# PCB_Schematic.net
KiCad netlist of a schematic drawn in Altium Designer
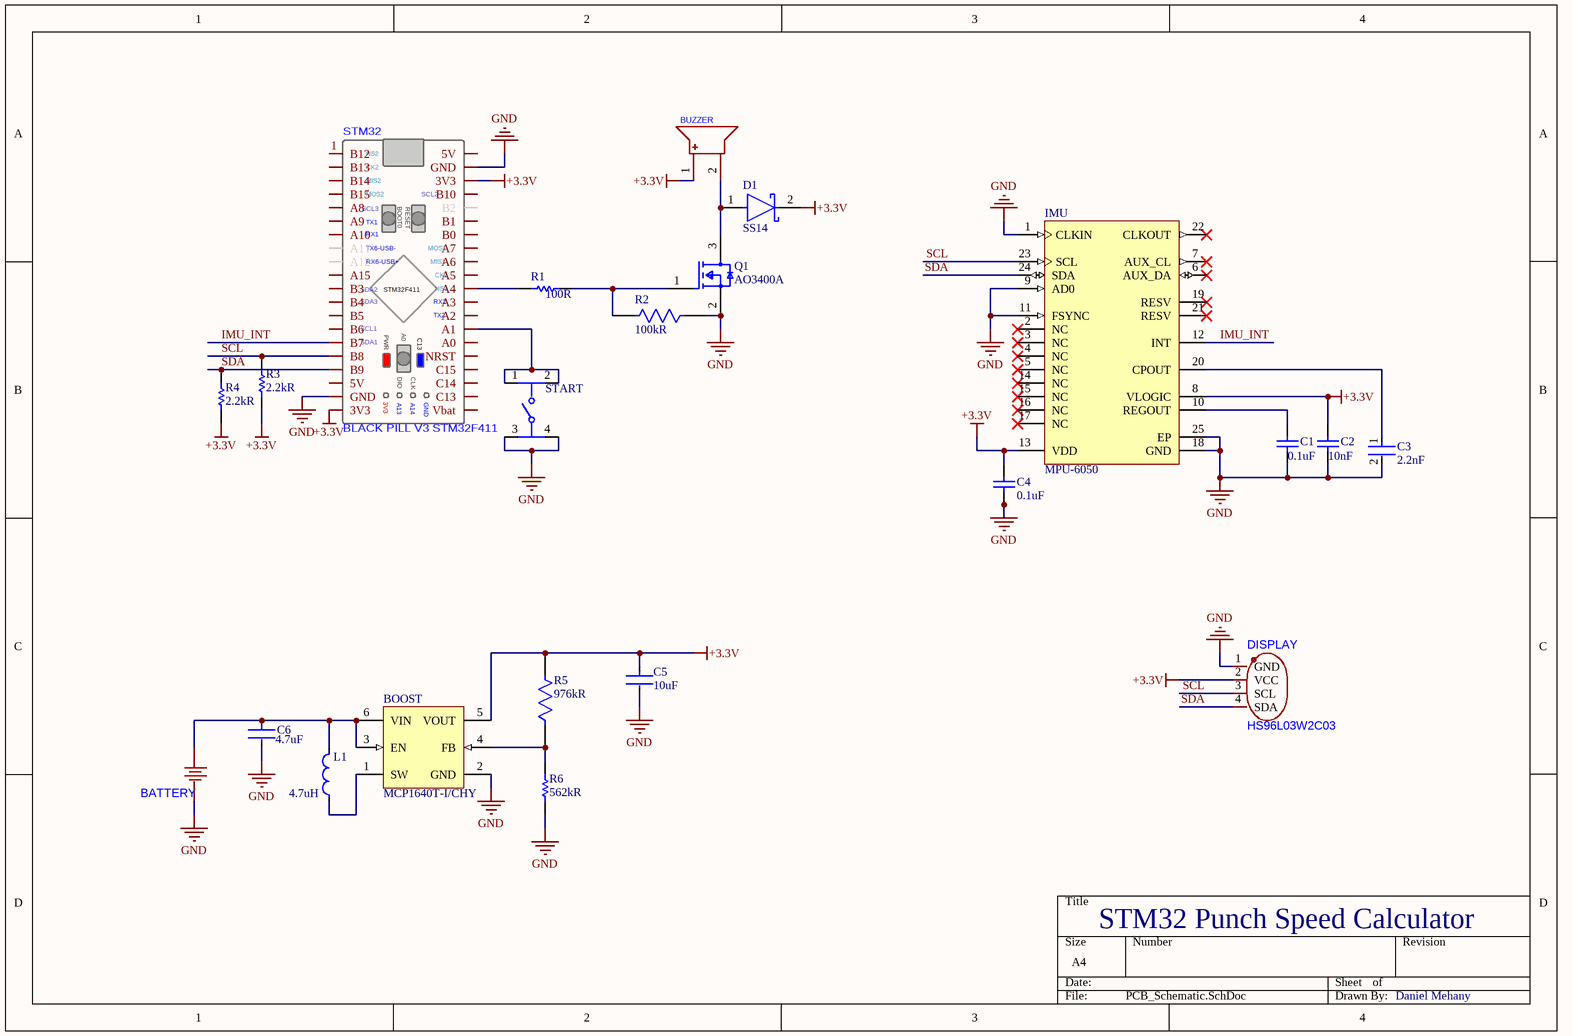
[diagram p0: PCB_Schematic.SchDoc]

(export (version "E")
  (design (tool "Eeschema 10.0.6"))
  (components
    (comp (ref "BATTERY")
      (value "BH-AAA-B5BA021")
      (footprint "BAT-SMD_BH-AAA-B5BA021")
      (fields (field (name "MANUFACTURER") "MYOUNG(美阳)") (field (name "JLCPCB PART #") "C7525446"))
      (libsource (lib "BH-AAA-B5BA0211_BH-AAA-B5BA021") (part "BH-AAA-B5BA021"))
    )
    (comp (ref "BOOST")
      (value "MCP1640T-I/CHY")
      (footprint "MCHP-SOT-23-CHY6_N")
      (fields (field (name "MANUFACTURER") "Microchip") (field (name "JLCPCB PART #") "C44365"))
      (libsource (lib "Altium Content Vault") (part "MCHP-MCP16XX-SOT-23-6"))
    )
    (comp (ref "BUZZER")
      (value "2.7kHz")
      (footprint "BUZ-SMD_L9.6-W9.6-LS10.0-R")
      (fields
        (field (name "MANUFACTURER") "华能")
        (field (name "MANUFACTURER PART") "MLT-9650")
        (field (name "JLCPCB PART #") "C96127")
      )
      (libsource (lib "beepsch") (part "MLT-9650"))
    )
    (comp (ref "C1")
      (value "CL05B104KO5NNNC")
      (footprint "CAPC1050X55X23ML05T13")
      (description "Chip Capacitor, 100 nF, +/- 10%, 16 V, -55 to 125 degC, 0402 (1005 Metric), RoHS, Tape and Reel")
      (fields
        (field (name "MANUFACTURER") "Samsung Electro-Mechanics")
        (field (name "CAP") "0.1uF")
        (field (name "JLCPCB PART #") "C1525")
      )
      (libsource (lib "Altium Content Vault") (part "CAP-NP-2"))
    )
    (comp (ref "C2")
      (value "10nF")
      (footprint "CAPC2013X75X45LL10T25")
      (fields
        (field (name "MANUFACTURER") "Samsung Electro-Mechanics")
        (field (name "JLCPCB PART #") "C1710")
      )
      (libsource (lib "Altium Content Vault") (part "CAP-NP-2"))
    )
    (comp (ref "C3")
      (value "2.2nF")
      (footprint "FP-C2012-060-0_2-IPC_B")
      (description "Multilayer Ceramic Capacitors 2.2nF ±5% 50V C0G SMD 0805")
      (fields (field (name "VOLTAGE") "50V") (field (name "TOLERANCE") "5%"))
      (libsource (lib "") (part "b4654b650e69147ec39a6b967a45e02_1"))
    )
    (comp (ref "C4")
      (value "CL05B104KO5NNNC")
      (footprint "CAPC1050X55X23ML05T13")
      (description "Chip Capacitor, 100 nF, +/- 10%, 16 V, -55 to 125 degC, 0402 (1005 Metric), RoHS, Tape and Reel")
      (fields
        (field (name "MANUFACTURER") "Samsung Electro-Mechanics")
        (field (name "CAP") "0.1uF")
        (field (name "JLCPCB PART #") "C1525")
      )
      (libsource (lib "Altium Content Vault") (part "CAP-NP-2"))
    )
    (comp (ref "C5")
      (value "10uF")
      (footprint "FP-CL31-IPC_C")
      (description "CAP CER 10UF 50V X5R 1206")
      (fields (field (name "TOLERANCE") "10%") (field (name "MANUFACTURER") "Samsung"))
      (libsource (lib "Altium Content Vault") (part "11868f565c42a9108669ba33697ecf6"))
    )
    (comp (ref "C6")
      (value "4.7uF")
      (footprint "FP-CL21-IPC_A")
      (description "CL21 Series 0805 4.7uF 25V ±10% Tolerance X5R Multilayer Ceramic Chip Capacitor")
      (fields (field (name "TOLERANCE") "10%") (field (name "JLCPCB PART #") "C1779"))
      (libsource (lib "Altium Content Vault") (part "b4654b650e69147ec39a6b967a45e02"))
    )
    (comp (ref "D1")
      (value "SS14")
      (footprint "FP-403AE-MFG")
      (description "DIODE SCHOTTKY 40V 1A SMA")
      (fields
        (field (name "MANUFACTURER") "ON Semiconductor")
        (field (name "OCTOPART") "https://octopart.com/ss14-on+semiconductor-29205033")
      )
      (libsource (lib "Altium Content Vault") (part "360ad2f4ac25a952324d13796385471"))
    )
    (comp (ref "DISPLAY")
      (value "HS96L03W2C03")
      (footprint "OLED-TH_L27.8-W27.2-P2.54_C9900033791")
      (fields (field (name "MANUFACTURER") "HS(汉昇)") (field (name "JLCPCB PART #") "C5248080"))
      (libsource (lib "HS96L03W2C031_HS96L03W2C03") (part "HS96L03W2C03"))
    )
    (comp (ref "IMU")
      (value "MPU-6050")
      (footprint "IS-QFN-24_V")
      (fields (field (name "MANUFACTURER") "InvenSense") (field (name "JLCPCB PART #") "C24112"))
      (libsource (lib "Altium Content Vault") (part "IS-MPU-6050-QFN-24"))
    )
    (comp (ref "L1")
      (value "4.7uH")
      (footprint "FP-LQM21PH_G0-IPC_C")
      (description "Multilayer Type Inductor for Power Lines, 0805 (2012), 4.7μH, 20%, 0.288Ω, 0.8A")
      (fields (field (name "TOLERANCE") "20%") (field (name "JLCPCB PART #") "C86090"))
      (libsource (lib "Altium Content Vault") (part "725321dda6339637d4d059423bc1c3c"))
    )
    (comp (ref "Q1")
      (value "AO3400A")
      (footprint "FP-SOT23-MFG")
      (description "MOSFET N-CH 30V 5.7A SOT23")
      (fields (field (name "JLCPCB PART #") "C20917"))
      (libsource (lib "Altium Content Vault") (part "0a9ea7c96deaaede766a5b531c28de0"))
    )
    (comp (ref "R1")
      (value "100R")
      (footprint "RESC1609X50X30ML8T20")
      (description "Chip Resistor, 100 Ohm, +/- 1%, 100 mW,-55 to 155 degC, 0603 (1608 Metric), RoHS, Tape and Ree")
      (fields (field (name "MANUFACTURER") "Vishay Semiconductor") (field (name "JLCPCB PART #") "C22775"))
      (libsource (lib "Altium Content Vault") (part "RES-2"))
    )
    (comp (ref "R2")
      (value "100kR")
      (footprint "FP-CRCW0603-HPe3-IPC_C")
      (description "RES Thick Film, 100kΩ, 1%, 0.33W, 100ppm/°C, 0603")
      (fields (field (name "TOLERANCE") "1%") (field (name "MANUFACTURER") "Uniroyal"))
      (libsource (lib "Altium Content Vault") (part "1029c3af85768c4190bb7ad29bc67b5"))
    )
    (comp (ref "R3")
      (value "2.2kR")
      (footprint "RESC1609X50X30NL10T20")
      (fields
        (field (name "PART NUMBER") "CRCW06032K20FKEA")
        (field (name "MANUFACTURER") "Vishay Dale")
        (field (name "JLCPCB PART #") "C4190")
      )
      (libsource (lib "Altium Content Vault") (part "RES"))
    )
    (comp (ref "R4")
      (value "2.2kR")
      (footprint "RESC1609X50X30NL10T20")
      (fields
        (field (name "PART NUMBER") "CRCW06032K20FKEA")
        (field (name "MANUFACTURER") "Vishay Dale")
        (field (name "JLCPCB PART #") "C4190")
      )
      (libsource (lib "Altium Content Vault") (part "RES"))
    )
    (comp (ref "R5")
      (value "976kR")
      (footprint "FP-AC0603-MFG")
      (description "RES 976KΩ 1.00% 0.1W 0603")
      (fields (field (name "TOLERANCE") "1%") (field (name "JLCPCB PART #") "C48922"))
      (libsource (lib "Altium Content Vault") (part "1029c3af85768c4190bb7ad29bc67b5"))
    )
    (comp (ref "R6")
      (value "562kR")
      (footprint "RESC1608X55X25NL10T15")
      (description "Chip Resistor, 562 KOhm, +/- 1%, 0.1 W, -55 to 155 degC, 0603 (1608 Metric), RoHS, Tape and Reel")
      (fields (field (name "JLCPCB PART #") "C185319"))
      (libsource (lib "Altium Content Vault") (part "RES-2"))
    )
    (comp (ref "START")
      (value "START")
      (footprint "FP-PTS645SM43SMTR92LFS-MFG")
      (description "SWITCH TACTILE SPST-NO 0.05A 12V")
      (fields (field (name "JLCPCB PART #") "C221880"))
      (libsource (lib "Altium Content Vault") (part "1adf0dd01260c80cf25a44bfd6b99ba"))
    )
    (comp (ref "STM32")
      (value "BLACK PILL V3 STM32F411")
      (footprint "BLACK PILL V3")
      (libsource (lib "BLACK-PILL-V3-STM32F411_2025-11-04") (part "BLACK PILL V3 STM32F411"))
    )
  )
  (nets
    (net (code "1") (name "+3.3V") (class "Default")
      (node (ref "BOOST") (pin "5") (pinfunction "VOUT_5") (pintype "power_in"))
      (node (ref "BUZZER") (pin "1") (pinfunction "1_1") (pintype "passive"))
      (node (ref "C2") (pin "2") (pinfunction "2_2") (pintype "passive"))
      (node (ref "C4") (pin "2") (pinfunction "2_2") (pintype "passive"))
      (node (ref "C5") (pin "1") (pinfunction "1_1") (pintype "passive"))
      (node (ref "D1") (pin "2") (pinfunction "C_2") (pintype "passive"))
      (node (ref "DISPLAY") (pin "2") (pinfunction "VCC_2") (pintype "passive"))
      (node (ref "IMU") (pin "13") (pinfunction "VDD_13") (pintype "power_in"))
      (node (ref "IMU") (pin "8") (pinfunction "VLOGIC_8") (pintype "power_in"))
      (node (ref "R3") (pin "1") (pinfunction "1_1") (pintype "passive"))
      (node (ref "R4") (pin "1") (pinfunction "1_1") (pintype "passive"))
      (node (ref "R5") (pin "2") (pinfunction "2_2") (pintype "passive"))
      (node (ref "STM32") (pin "20") (pinfunction "3V3_20") (pintype "passive"))
      (node (ref "STM32") (pin "23") (pinfunction "3V3_23") (pintype "passive"))
    )
    (net (code "2") (name "/IMU_INT") (class "Default")
      (node (ref "IMU") (pin "12") (pinfunction "INT_12") (pintype "open_collector"))
      (node (ref "STM32") (pin "15") (pinfunction "B7_15") (pintype "passive"))
    )
    (net (code "3") (name "/SCL") (class "Default")
      (node (ref "DISPLAY") (pin "3") (pinfunction "SCL_3") (pintype "passive"))
      (node (ref "IMU") (pin "23") (pinfunction "SCL_23") (pintype "input"))
      (node (ref "R3") (pin "2") (pinfunction "2_2") (pintype "passive"))
      (node (ref "STM32") (pin "16") (pinfunction "B8_16") (pintype "passive"))
    )
    (net (code "4") (name "/SDA") (class "Default")
      (node (ref "DISPLAY") (pin "4") (pinfunction "SDA_4") (pintype "passive"))
      (node (ref "IMU") (pin "24") (pinfunction "SDA_24") (pintype "bidirectional"))
      (node (ref "R4") (pin "2") (pinfunction "2_2") (pintype "passive"))
      (node (ref "STM32") (pin "17") (pinfunction "B9_17") (pintype "passive"))
    )
    (net (code "5") (name "GND") (class "Default")
      (node (ref "BATTERY") (pin "2") (pinfunction "2_2") (pintype "passive"))
      (node (ref "BOOST") (pin "2") (pinfunction "GND_2") (pintype "power_in"))
      (node (ref "C1") (pin "1") (pinfunction "1_1") (pintype "passive"))
      (node (ref "C2") (pin "1") (pinfunction "1_1") (pintype "passive"))
      (node (ref "C3") (pin "2") (pinfunction "2_2") (pintype "passive"))
      (node (ref "C4") (pin "1") (pinfunction "1_1") (pintype "passive"))
      (node (ref "C5") (pin "2") (pinfunction "2_2") (pintype "passive"))
      (node (ref "C6") (pin "2") (pinfunction "2_2") (pintype "passive"))
      (node (ref "DISPLAY") (pin "1") (pinfunction "GND_1") (pintype "passive"))
      (node (ref "IMU") (pin "1") (pinfunction "CLKIN_1") (pintype "input"))
      (node (ref "IMU") (pin "11") (pinfunction "FSYNC_11") (pintype "input"))
      (node (ref "IMU") (pin "18") (pinfunction "GND_18") (pintype "power_in"))
      (node (ref "IMU") (pin "25") (pinfunction "EP_25") (pintype "power_in"))
      (node (ref "IMU") (pin "9") (pinfunction "AD0_9") (pintype "input"))
      (node (ref "Q1") (pin "2") (pinfunction "S_2") (pintype "passive"))
      (node (ref "R2") (pin "1") (pinfunction "1_1") (pintype "passive"))
      (node (ref "R6") (pin "1") (pinfunction "1_1") (pintype "passive"))
      (node (ref "START") (pin "3") (pinfunction "3_3") (pintype "passive"))
      (node (ref "START") (pin "4") (pinfunction "4_4") (pintype "passive"))
      (node (ref "STM32") (pin "19") (pinfunction "GND_19") (pintype "passive"))
      (node (ref "STM32") (pin "22") (pinfunction "GND_22") (pintype "passive"))
    )
    (net (code "6") (name "Net-(BOOST-EN)") (class "Default")
      (node (ref "BATTERY") (pin "1") (pinfunction "1_1") (pintype "passive"))
      (node (ref "BOOST") (pin "3") (pinfunction "EN_3") (pintype "input"))
      (node (ref "BOOST") (pin "6") (pinfunction "VIN_6") (pintype "power_in"))
      (node (ref "C6") (pin "1") (pinfunction "1_1") (pintype "passive"))
      (node (ref "L1") (pin "2") (pinfunction "2_2") (pintype "passive"))
    )
    (net (code "7") (name "Net-(BOOST-FB)") (class "Default")
      (node (ref "BOOST") (pin "4") (pinfunction "FB_4") (pintype "input"))
      (node (ref "R5") (pin "1") (pinfunction "1_1") (pintype "passive"))
      (node (ref "R6") (pin "2") (pinfunction "2_2") (pintype "passive"))
    )
    (net (code "8") (name "Net-(BOOST-SW)") (class "Default")
      (node (ref "BOOST") (pin "1") (pinfunction "SW_1") (pintype "power_in"))
      (node (ref "L1") (pin "1") (pinfunction "1_1") (pintype "passive"))
    )
    (net (code "9") (name "Net-(D1-A)") (class "Default")
      (node (ref "BUZZER") (pin "2") (pinfunction "2_2") (pintype "passive"))
      (node (ref "D1") (pin "1") (pinfunction "A_1") (pintype "passive"))
      (node (ref "Q1") (pin "3") (pinfunction "D_3") (pintype "passive"))
    )
    (net (code "10") (name "Net-(IMU-CPOUT)") (class "Default")
      (node (ref "C3") (pin "1") (pinfunction "1_1") (pintype "passive"))
      (node (ref "IMU") (pin "20") (pinfunction "CPOUT_20") (pintype "passive"))
    )
    (net (code "11") (name "Net-(IMU-REGOUT)") (class "Default")
      (node (ref "C1") (pin "2") (pinfunction "2_2") (pintype "passive"))
      (node (ref "IMU") (pin "10") (pinfunction "REGOUT_10") (pintype "passive"))
    )
    (net (code "12") (name "Net-(Q1-G)") (class "Default")
      (node (ref "Q1") (pin "1") (pinfunction "G_1") (pintype "passive"))
      (node (ref "R1") (pin "2") (pinfunction "2_2") (pintype "passive"))
      (node (ref "R2") (pin "2") (pinfunction "2_2") (pintype "passive"))
    )
    (net (code "13") (name "Net-(STM32-A1)") (class "Default")
      (node (ref "START") (pin "1") (pinfunction "1_1") (pintype "passive"))
      (node (ref "START") (pin "2") (pinfunction "2_2") (pintype "passive"))
      (node (ref "STM32") (pin "34") (pinfunction "A1_34") (pintype "passive"))
    )
    (net (code "14") (name "Net-(STM32-A4)") (class "Default")
      (node (ref "R1") (pin "1") (pinfunction "1_1") (pintype "passive"))
      (node (ref "STM32") (pin "31") (pinfunction "A4_31") (pintype "passive"))
    )
    (net (code "15") (name "unconnected-(IMU-AUX_CL-Pad7)") (class "Default")
      (node (ref "IMU") (pin "7") (pinfunction "AUX_CL_7") (pintype "output+no_connect"))
    )
    (net (code "16") (name "unconnected-(IMU-AUX_DA-Pad6)") (class "Default")
      (node (ref "IMU") (pin "6") (pinfunction "AUX_DA_6") (pintype "bidirectional+no_connect"))
    )
    (net (code "17") (name "unconnected-(IMU-CLKOUT-Pad22)") (class "Default")
      (node (ref "IMU") (pin "22") (pinfunction "CLKOUT_22") (pintype "output+no_connect"))
    )
    (net (code "18") (name "unconnected-(IMU-NC-Pad2)") (class "Default")
      (node (ref "IMU") (pin "2") (pinfunction "NC_2") (pintype "passive+no_connect"))
    )
    (net (code "19") (name "unconnected-(IMU-NC-Pad3)") (class "Default")
      (node (ref "IMU") (pin "3") (pinfunction "NC_3") (pintype "passive+no_connect"))
    )
    (net (code "20") (name "unconnected-(IMU-NC-Pad4)") (class "Default")
      (node (ref "IMU") (pin "4") (pinfunction "NC_4") (pintype "passive+no_connect"))
    )
    (net (code "21") (name "unconnected-(IMU-NC-Pad5)") (class "Default")
      (node (ref "IMU") (pin "5") (pinfunction "NC_5") (pintype "passive+no_connect"))
    )
    (net (code "22") (name "unconnected-(IMU-NC-Pad14)") (class "Default")
      (node (ref "IMU") (pin "14") (pinfunction "NC_14") (pintype "passive+no_connect"))
    )
    (net (code "23") (name "unconnected-(IMU-NC-Pad15)") (class "Default")
      (node (ref "IMU") (pin "15") (pinfunction "NC_15") (pintype "passive+no_connect"))
    )
    (net (code "24") (name "unconnected-(IMU-NC-Pad16)") (class "Default")
      (node (ref "IMU") (pin "16") (pinfunction "NC_16") (pintype "passive+no_connect"))
    )
    (net (code "25") (name "unconnected-(IMU-NC-Pad17)") (class "Default")
      (node (ref "IMU") (pin "17") (pinfunction "NC_17") (pintype "passive+no_connect"))
    )
    (net (code "26") (name "unconnected-(IMU-RESV-Pad19)") (class "Default")
      (node (ref "IMU") (pin "19") (pinfunction "RESV_19") (pintype "passive+no_connect"))
    )
    (net (code "27") (name "unconnected-(IMU-RESV-Pad21)") (class "Default")
      (node (ref "IMU") (pin "21") (pinfunction "RESV_21") (pintype "passive+no_connect"))
    )
    (net (code "28") (name "unconnected-(STM32-5V-Pad18)") (class "Default")
      (node (ref "STM32") (pin "18") (pinfunction "5V_18") (pintype "passive"))
    )
    (net (code "29") (name "unconnected-(STM32-5V-Pad21)") (class "Default")
      (node (ref "STM32") (pin "21") (pinfunction "5V_21") (pintype "passive"))
    )
    (net (code "30") (name "unconnected-(STM32-A0-Pad35)") (class "Default")
      (node (ref "STM32") (pin "35") (pinfunction "A0_35") (pintype "passive"))
    )
    (net (code "31") (name "unconnected-(STM32-A2-Pad33)") (class "Default")
      (node (ref "STM32") (pin "33") (pinfunction "A2_33") (pintype "passive"))
    )
    (net (code "32") (name "unconnected-(STM32-A3-Pad32)") (class "Default")
      (node (ref "STM32") (pin "32") (pinfunction "A3_32") (pintype "passive"))
    )
    (net (code "33") (name "unconnected-(STM32-A5-Pad30)") (class "Default")
      (node (ref "STM32") (pin "30") (pinfunction "A5_30") (pintype "passive"))
    )
    (net (code "34") (name "unconnected-(STM32-A6-Pad29)") (class "Default")
      (node (ref "STM32") (pin "29") (pinfunction "A6_29") (pintype "passive"))
    )
    (net (code "35") (name "unconnected-(STM32-A7-Pad28)") (class "Default")
      (node (ref "STM32") (pin "28") (pinfunction "A7_28") (pintype "passive"))
    )
    (net (code "36") (name "unconnected-(STM32-A8-Pad5)") (class "Default")
      (node (ref "STM32") (pin "5") (pinfunction "A8_5") (pintype "passive"))
    )
    (net (code "37") (name "unconnected-(STM32-A9-Pad6)") (class "Default")
      (node (ref "STM32") (pin "6") (pinfunction "A9_6") (pintype "passive"))
    )
    (net (code "38") (name "unconnected-(STM32-A10-Pad7)") (class "Default")
      (node (ref "STM32") (pin "7") (pinfunction "A10_7") (pintype "passive"))
    )
    (net (code "39") (name "unconnected-(STM32-A11-Pad8)") (class "Default")
      (node (ref "STM32") (pin "8") (pinfunction "A11_8") (pintype "passive"))
    )
    (net (code "40") (name "unconnected-(STM32-A12-Pad9)") (class "Default")
      (node (ref "STM32") (pin "9") (pinfunction "A12_9") (pintype "passive"))
    )
    (net (code "41") (name "unconnected-(STM32-A15-Pad10)") (class "Default")
      (node (ref "STM32") (pin "10") (pinfunction "A15_10") (pintype "passive"))
    )
    (net (code "42") (name "unconnected-(STM32-B0-Pad27)") (class "Default")
      (node (ref "STM32") (pin "27") (pinfunction "B0_27") (pintype "passive"))
    )
    (net (code "43") (name "unconnected-(STM32-B1-Pad26)") (class "Default")
      (node (ref "STM32") (pin "26") (pinfunction "B1_26") (pintype "passive"))
    )
    (net (code "44") (name "unconnected-(STM32-B2-Pad25)") (class "Default")
      (node (ref "STM32") (pin "25") (pinfunction "B2_25") (pintype "passive"))
    )
    (net (code "45") (name "unconnected-(STM32-B3-Pad11)") (class "Default")
      (node (ref "STM32") (pin "11") (pinfunction "B3_11") (pintype "passive"))
    )
    (net (code "46") (name "unconnected-(STM32-B4-Pad12)") (class "Default")
      (node (ref "STM32") (pin "12") (pinfunction "B4_12") (pintype "passive"))
    )
    (net (code "47") (name "unconnected-(STM32-B5-Pad13)") (class "Default")
      (node (ref "STM32") (pin "13") (pinfunction "B5_13") (pintype "passive"))
    )
    (net (code "48") (name "unconnected-(STM32-B6-Pad14)") (class "Default")
      (node (ref "STM32") (pin "14") (pinfunction "B6_14") (pintype "passive"))
    )
    (net (code "49") (name "unconnected-(STM32-B10-Pad24)") (class "Default")
      (node (ref "STM32") (pin "24") (pinfunction "B10_24") (pintype "passive"))
    )
    (net (code "50") (name "unconnected-(STM32-B12-Pad1)") (class "Default")
      (node (ref "STM32") (pin "1") (pinfunction "B12_1") (pintype "passive"))
    )
    (net (code "51") (name "unconnected-(STM32-B13-Pad2)") (class "Default")
      (node (ref "STM32") (pin "2") (pinfunction "B13_2") (pintype "passive"))
    )
    (net (code "52") (name "unconnected-(STM32-B14-Pad3)") (class "Default")
      (node (ref "STM32") (pin "3") (pinfunction "B14_3") (pintype "passive"))
    )
    (net (code "53") (name "unconnected-(STM32-B15-Pad4)") (class "Default")
      (node (ref "STM32") (pin "4") (pinfunction "B15_4") (pintype "passive"))
    )
    (net (code "54") (name "unconnected-(STM32-C13-Pad39)") (class "Default")
      (node (ref "STM32") (pin "39") (pinfunction "C13_39") (pintype "passive"))
    )
    (net (code "55") (name "unconnected-(STM32-C14-Pad38)") (class "Default")
      (node (ref "STM32") (pin "38") (pinfunction "C14_38") (pintype "passive"))
    )
    (net (code "56") (name "unconnected-(STM32-C15-Pad37)") (class "Default")
      (node (ref "STM32") (pin "37") (pinfunction "C15_37") (pintype "passive"))
    )
    (net (code "57") (name "unconnected-(STM32-NRST-Pad36)") (class "Default")
      (node (ref "STM32") (pin "36") (pinfunction "NRST_36") (pintype "passive"))
    )
    (net (code "58") (name "unconnected-(STM32-Vbat-Pad40)") (class "Default")
      (node (ref "STM32") (pin "40") (pinfunction "Vbat_40") (pintype "passive"))
    )
  )
)
